# LED.net
KiCad netlist of a schematic drawn in Altium Designer
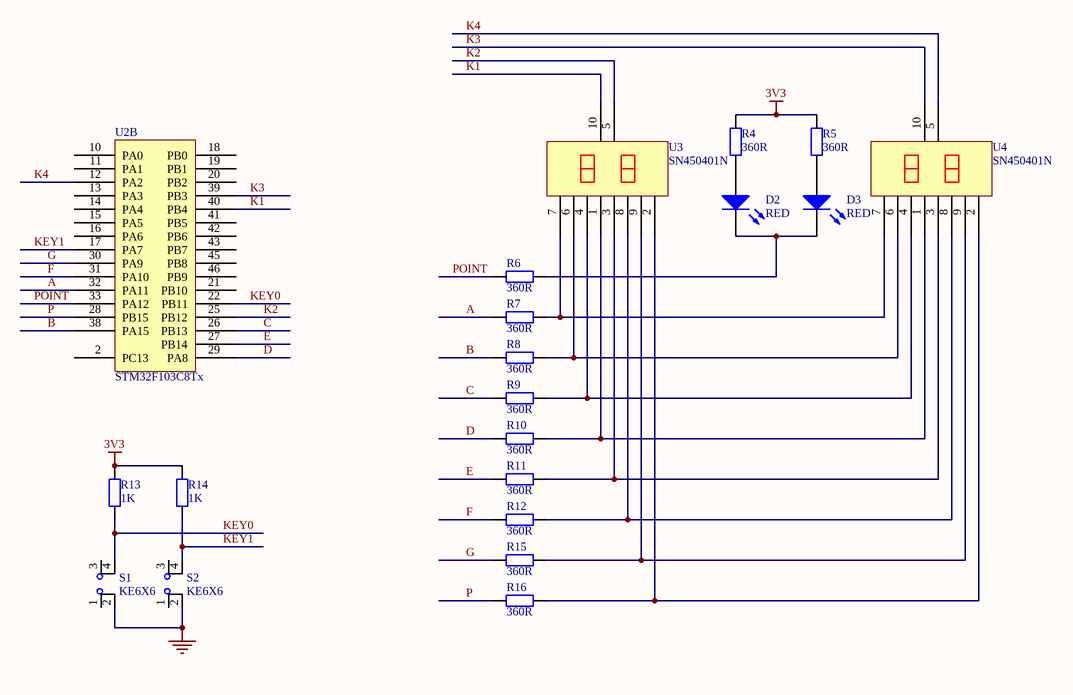
[diagram p0: LED.SchDoc]

(export (version "E")
  (design (tool "Eeschema 10.0.6"))
  (components
    (comp (ref "D2")
      (value "RED")
      (footprint "MicroControl:LED3MM-RED")
      (description "Typical INFRARED GaAs LED")
      (fields (field (name "PUBLISHER") "Altium Limited"))
      (libsource (lib "Miscellaneous Devices") (part "LED0"))
    )
    (comp (ref "D3")
      (value "RED")
      (footprint "MicroControl:LED3MM-RED")
      (description "Typical INFRARED GaAs LED")
      (fields (field (name "PUBLISHER") "Altium Limited"))
      (libsource (lib "Miscellaneous Devices") (part "LED0"))
    )
    (comp (ref "R4")
      (value "360R")
      (footprint "MicroControl:R0603")
      (description "Resistor")
      (fields (field (name "PUBLISHER") "Altium Limited"))
      (libsource (lib "") (part "Res2_1"))
    )
    (comp (ref "R5")
      (value "360R")
      (footprint "MicroControl:R0603")
      (description "Resistor")
      (fields (field (name "PUBLISHER") "Altium Limited"))
      (libsource (lib "") (part "Res2_1"))
    )
    (comp (ref "R6")
      (value "360R")
      (footprint "MicroControl:R0603")
      (description "Resistor")
      (fields (field (name "PUBLISHER") "Altium Limited"))
      (libsource (lib "Miscellaneous Devices") (part "Res2"))
    )
    (comp (ref "R7")
      (value "360R")
      (footprint "MicroControl:R0603")
      (description "Resistor")
      (fields (field (name "PUBLISHER") "Altium Limited"))
      (libsource (lib "Miscellaneous Devices") (part "Res2"))
    )
    (comp (ref "R8")
      (value "360R")
      (footprint "MicroControl:R0603")
      (description "Resistor")
      (fields (field (name "PUBLISHER") "Altium Limited"))
      (libsource (lib "Miscellaneous Devices") (part "Res2"))
    )
    (comp (ref "R9")
      (value "360R")
      (footprint "MicroControl:R0603")
      (description "Resistor")
      (fields (field (name "PUBLISHER") "Altium Limited"))
      (libsource (lib "Miscellaneous Devices") (part "Res2"))
    )
    (comp (ref "R10")
      (value "360R")
      (footprint "MicroControl:R0603")
      (description "Resistor")
      (fields (field (name "PUBLISHER") "Altium Limited"))
      (libsource (lib "Miscellaneous Devices") (part "Res2"))
    )
    (comp (ref "R11")
      (value "360R")
      (footprint "MicroControl:R0603")
      (description "Resistor")
      (fields (field (name "PUBLISHER") "Altium Limited"))
      (libsource (lib "Miscellaneous Devices") (part "Res2"))
    )
    (comp (ref "R12")
      (value "360R")
      (footprint "MicroControl:R0603")
      (description "Resistor")
      (fields (field (name "PUBLISHER") "Altium Limited"))
      (libsource (lib "Miscellaneous Devices") (part "Res2"))
    )
    (comp (ref "R13")
      (value "1K")
      (footprint "MicroControl:R0603")
      (description "Resistor")
      (fields (field (name "PUBLISHER") "Altium Limited"))
      (libsource (lib "") (part "Res2_1"))
    )
    (comp (ref "R14")
      (value "1K")
      (footprint "MicroControl:R0603")
      (description "Resistor")
      (fields (field (name "PUBLISHER") "Altium Limited"))
      (libsource (lib "") (part "Res2_1"))
    )
    (comp (ref "R15")
      (value "360R")
      (footprint "MicroControl:R0603")
      (description "Resistor")
      (fields (field (name "PUBLISHER") "Altium Limited"))
      (libsource (lib "Miscellaneous Devices") (part "Res2"))
    )
    (comp (ref "R16")
      (value "360R")
      (footprint "MicroControl:R0603")
      (description "Resistor")
      (fields (field (name "PUBLISHER") "Altium Limited"))
      (libsource (lib "Miscellaneous Devices") (part "Res2"))
    )
    (comp (ref "S1")
      (value "KE6X6")
      (footprint "MicroControl:KE6X6-SMT")
      (libsource (lib "ClockSchematicLib") (part "KE6X6-SMT"))
    )
    (comp (ref "S2")
      (value "KE6X6")
      (footprint "MicroControl:KE6X6-SMT")
      (libsource (lib "ClockSchematicLib") (part "KE6X6-SMT"))
    )
    (comp (ref "U2")
      (value "STM32F103C8Tx")
      (footprint "Integrated_Circuit:PQFP48")
      (libsource (lib "yinhaonanLib") (part "STM32F103C8Tx"))
    )
    (comp (ref "U3")
      (value "SN450401N")
      (footprint "clockPCBLib:SMG 0.56-2P")
      (libsource (lib "ClockSchematicLib") (part "SN450401N"))
    )
    (comp (ref "U4")
      (value "SN450401N")
      (footprint "clockPCBLib:SMG 0.56-2P")
      (libsource (lib "ClockSchematicLib") (part "SN450401N"))
    )
  )
  (nets
    (net (code "1") (name "/A") (class "Default")
      (node (ref "R7") (pin "1") (pinfunction "1_1") (pintype "passive"))
      (node (ref "U2") (pin "32") (pinfunction "PA11_32") (pintype "passive"))
    )
    (net (code "2") (name "/B") (class "Default")
      (node (ref "R8") (pin "1") (pinfunction "1_1") (pintype "passive"))
      (node (ref "U2") (pin "38") (pinfunction "PA15_38") (pintype "passive"))
    )
    (net (code "3") (name "/C") (class "Default")
      (node (ref "R9") (pin "1") (pinfunction "1_1") (pintype "passive"))
      (node (ref "U2") (pin "26") (pinfunction "PB13_26") (pintype "passive"))
    )
    (net (code "4") (name "/D") (class "Default")
      (node (ref "R10") (pin "1") (pinfunction "1_1") (pintype "passive"))
      (node (ref "U2") (pin "29") (pinfunction "PA8_29") (pintype "passive"))
    )
    (net (code "5") (name "/E") (class "Default")
      (node (ref "R11") (pin "1") (pinfunction "1_1") (pintype "passive"))
      (node (ref "U2") (pin "27") (pinfunction "PB14_27") (pintype "passive"))
    )
    (net (code "6") (name "/F") (class "Default")
      (node (ref "R12") (pin "1") (pinfunction "1_1") (pintype "passive"))
      (node (ref "U2") (pin "31") (pinfunction "PA10_31") (pintype "passive"))
    )
    (net (code "7") (name "/G") (class "Default")
      (node (ref "R15") (pin "1") (pinfunction "1_1") (pintype "passive"))
      (node (ref "U2") (pin "30") (pinfunction "PA9_30") (pintype "passive"))
    )
    (net (code "8") (name "/K1") (class "Default")
      (node (ref "U2") (pin "40") (pinfunction "PB4_40") (pintype "passive"))
      (node (ref "U3") (pin "10") (pinfunction "10_10") (pintype "passive"))
    )
    (net (code "9") (name "/K2") (class "Default")
      (node (ref "U2") (pin "25") (pinfunction "PB12_25") (pintype "passive"))
      (node (ref "U3") (pin "5") (pinfunction "5_5") (pintype "passive"))
    )
    (net (code "10") (name "/K3") (class "Default")
      (node (ref "U2") (pin "39") (pinfunction "PB3_39") (pintype "passive"))
      (node (ref "U4") (pin "10") (pinfunction "10_10") (pintype "passive"))
    )
    (net (code "11") (name "/K4") (class "Default")
      (node (ref "U2") (pin "12") (pinfunction "PA2_12") (pintype "passive"))
      (node (ref "U4") (pin "5") (pinfunction "5_5") (pintype "passive"))
    )
    (net (code "12") (name "/KEY0") (class "Default")
      (node (ref "R13") (pin "1") (pinfunction "1_1") (pintype "passive"))
      (node (ref "S1") (pin "4") (pinfunction "4_4") (pintype "passive"))
      (node (ref "U2") (pin "22") (pinfunction "PB11_22") (pintype "passive"))
    )
    (net (code "13") (name "/KEY1") (class "Default")
      (node (ref "R14") (pin "1") (pinfunction "1_1") (pintype "passive"))
      (node (ref "S2") (pin "4") (pinfunction "4_4") (pintype "passive"))
      (node (ref "U2") (pin "17") (pinfunction "PA7_17") (pintype "passive"))
    )
    (net (code "14") (name "/P") (class "Default")
      (node (ref "R16") (pin "1") (pinfunction "1_1") (pintype "passive"))
      (node (ref "U2") (pin "28") (pinfunction "PB15_28") (pintype "passive"))
    )
    (net (code "15") (name "/POINT") (class "Default")
      (node (ref "R6") (pin "1") (pinfunction "1_1") (pintype "passive"))
      (node (ref "U2") (pin "33") (pinfunction "PA12_33") (pintype "passive"))
    )
    (net (code "16") (name "3V3") (class "Default")
      (node (ref "R13") (pin "2") (pinfunction "2_2") (pintype "passive"))
      (node (ref "R14") (pin "2") (pinfunction "2_2") (pintype "passive"))
      (node (ref "R4") (pin "2") (pinfunction "2_2") (pintype "passive"))
      (node (ref "R5") (pin "2") (pinfunction "2_2") (pintype "passive"))
    )
    (net (code "17") (name "GND") (class "Default")
      (node (ref "S1") (pin "2") (pinfunction "2_2") (pintype "passive"))
      (node (ref "S2") (pin "2") (pinfunction "2_2") (pintype "passive"))
    )
    (net (code "18") (name "Net-(D2-A)") (class "Default")
      (node (ref "D2") (pin "1") (pinfunction "A_1") (pintype "passive"))
      (node (ref "R4") (pin "1") (pinfunction "1_1") (pintype "passive"))
    )
    (net (code "19") (name "Net-(D2-K)") (class "Default")
      (node (ref "D2") (pin "2") (pinfunction "K_2") (pintype "passive"))
      (node (ref "D3") (pin "2") (pinfunction "K_2") (pintype "passive"))
      (node (ref "R6") (pin "2") (pinfunction "2_2") (pintype "passive"))
    )
    (net (code "20") (name "Net-(D3-A)") (class "Default")
      (node (ref "D3") (pin "1") (pinfunction "A_1") (pintype "passive"))
      (node (ref "R5") (pin "1") (pinfunction "1_1") (pintype "passive"))
    )
    (net (code "21") (name "Net-(R7-Pad2)") (class "Default")
      (node (ref "R7") (pin "2") (pinfunction "2_2") (pintype "passive"))
      (node (ref "U3") (pin "7") (pinfunction "7_7") (pintype "passive"))
      (node (ref "U4") (pin "7") (pinfunction "7_7") (pintype "passive"))
    )
    (net (code "22") (name "Net-(R8-Pad2)") (class "Default")
      (node (ref "R8") (pin "2") (pinfunction "2_2") (pintype "passive"))
      (node (ref "U3") (pin "6") (pinfunction "6_6") (pintype "passive"))
      (node (ref "U4") (pin "6") (pinfunction "6_6") (pintype "passive"))
    )
    (net (code "23") (name "Net-(R9-Pad2)") (class "Default")
      (node (ref "R9") (pin "2") (pinfunction "2_2") (pintype "passive"))
      (node (ref "U3") (pin "4") (pinfunction "4_4") (pintype "passive"))
      (node (ref "U4") (pin "4") (pinfunction "4_4") (pintype "passive"))
    )
    (net (code "24") (name "Net-(R10-Pad2)") (class "Default")
      (node (ref "R10") (pin "2") (pinfunction "2_2") (pintype "passive"))
      (node (ref "U3") (pin "1") (pinfunction "1_1") (pintype "passive"))
      (node (ref "U4") (pin "1") (pinfunction "1_1") (pintype "passive"))
    )
    (net (code "25") (name "Net-(R11-Pad2)") (class "Default")
      (node (ref "R11") (pin "2") (pinfunction "2_2") (pintype "passive"))
      (node (ref "U3") (pin "3") (pinfunction "3_3") (pintype "passive"))
      (node (ref "U4") (pin "3") (pinfunction "3_3") (pintype "passive"))
    )
    (net (code "26") (name "Net-(R12-Pad2)") (class "Default")
      (node (ref "R12") (pin "2") (pinfunction "2_2") (pintype "passive"))
      (node (ref "U3") (pin "8") (pinfunction "8_8") (pintype "passive"))
      (node (ref "U4") (pin "8") (pinfunction "8_8") (pintype "passive"))
    )
    (net (code "27") (name "Net-(R15-Pad2)") (class "Default")
      (node (ref "R15") (pin "2") (pinfunction "2_2") (pintype "passive"))
      (node (ref "U3") (pin "9") (pinfunction "9_9") (pintype "passive"))
      (node (ref "U4") (pin "9") (pinfunction "9_9") (pintype "passive"))
    )
    (net (code "28") (name "Net-(R16-Pad2)") (class "Default")
      (node (ref "R16") (pin "2") (pinfunction "2_2") (pintype "passive"))
      (node (ref "U3") (pin "2") (pinfunction "2_2") (pintype "passive"))
      (node (ref "U4") (pin "2") (pinfunction "2_2") (pintype "passive"))
    )
    (net (code "29") (name "unconnected-(S1-Pad1)") (class "Default")
      (node (ref "S1") (pin "1") (pinfunction "1_1") (pintype "passive"))
    )
    (net (code "30") (name "unconnected-(S1-Pad3)") (class "Default")
      (node (ref "S1") (pin "3") (pinfunction "3_3") (pintype "passive"))
    )
    (net (code "31") (name "unconnected-(S2-Pad1)") (class "Default")
      (node (ref "S2") (pin "1") (pinfunction "1_1") (pintype "passive"))
    )
    (net (code "32") (name "unconnected-(S2-Pad3)") (class "Default")
      (node (ref "S2") (pin "3") (pinfunction "3_3") (pintype "passive"))
    )
    (net (code "33") (name "unconnected-(U2B-PA0-Pad10)") (class "Default")
      (node (ref "U2") (pin "10") (pinfunction "PA0_10") (pintype "passive"))
    )
    (net (code "34") (name "unconnected-(U2B-PA1-Pad11)") (class "Default")
      (node (ref "U2") (pin "11") (pinfunction "PA1_11") (pintype "passive"))
    )
    (net (code "35") (name "unconnected-(U2B-PA3-Pad13)") (class "Default")
      (node (ref "U2") (pin "13") (pinfunction "PA3_13") (pintype "passive"))
    )
    (net (code "36") (name "unconnected-(U2B-PA4-Pad14)") (class "Default")
      (node (ref "U2") (pin "14") (pinfunction "PA4_14") (pintype "passive"))
    )
    (net (code "37") (name "unconnected-(U2B-PA5-Pad15)") (class "Default")
      (node (ref "U2") (pin "15") (pinfunction "PA5_15") (pintype "passive"))
    )
    (net (code "38") (name "unconnected-(U2B-PA6-Pad16)") (class "Default")
      (node (ref "U2") (pin "16") (pinfunction "PA6_16") (pintype "passive"))
    )
    (net (code "39") (name "unconnected-(U2B-PB0-Pad18)") (class "Default")
      (node (ref "U2") (pin "18") (pinfunction "PB0_18") (pintype "passive"))
    )
    (net (code "40") (name "unconnected-(U2B-PB1-Pad19)") (class "Default")
      (node (ref "U2") (pin "19") (pinfunction "PB1_19") (pintype "passive"))
    )
    (net (code "41") (name "unconnected-(U2B-PB2-Pad20)") (class "Default")
      (node (ref "U2") (pin "20") (pinfunction "PB2_20") (pintype "passive"))
    )
    (net (code "42") (name "unconnected-(U2B-PB5-Pad41)") (class "Default")
      (node (ref "U2") (pin "41") (pinfunction "PB5_41") (pintype "passive"))
    )
    (net (code "43") (name "unconnected-(U2B-PB6-Pad42)") (class "Default")
      (node (ref "U2") (pin "42") (pinfunction "PB6_42") (pintype "passive"))
    )
    (net (code "44") (name "unconnected-(U2B-PB7-Pad43)") (class "Default")
      (node (ref "U2") (pin "43") (pinfunction "PB7_43") (pintype "passive"))
    )
    (net (code "45") (name "unconnected-(U2B-PB8-Pad45)") (class "Default")
      (node (ref "U2") (pin "45") (pinfunction "PB8_45") (pintype "passive"))
    )
    (net (code "46") (name "unconnected-(U2B-PB9-Pad46)") (class "Default")
      (node (ref "U2") (pin "46") (pinfunction "PB9_46") (pintype "passive"))
    )
    (net (code "47") (name "unconnected-(U2B-PB10-Pad21)") (class "Default")
      (node (ref "U2") (pin "21") (pinfunction "PB10_21") (pintype "passive"))
    )
    (net (code "48") (name "unconnected-(U2B-PC13-Pad2)") (class "Default")
      (node (ref "U2") (pin "2") (pinfunction "PC13_2") (pintype "passive"))
    )
  )
)
